# MYBOARD_04-Other_Function.net
KiCad netlist of a schematic drawn in Altium Designer
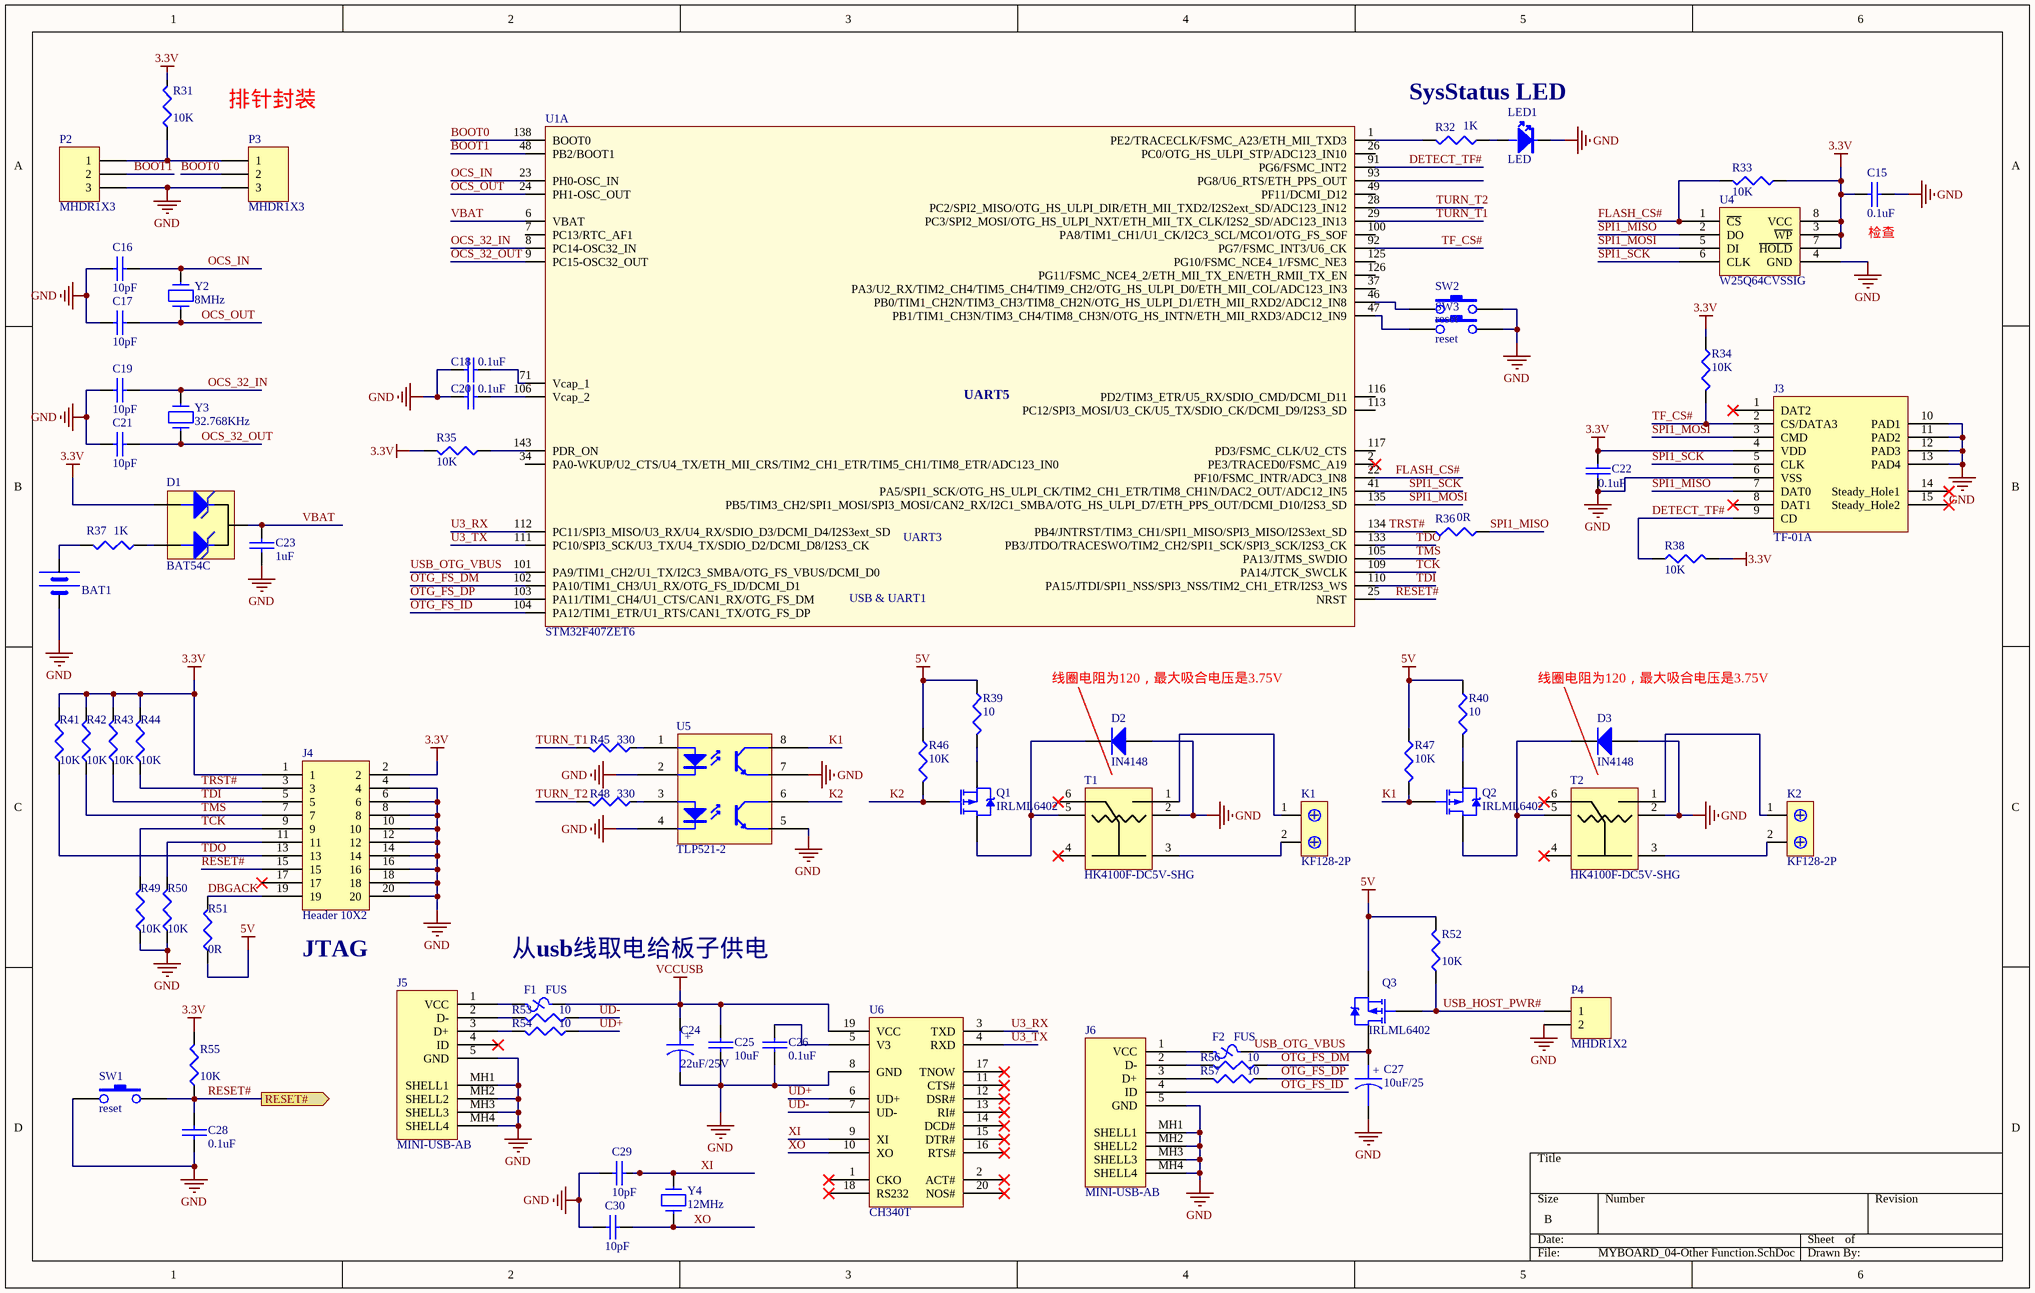
[diagram p0: MYBOARD_04-Other Function.SchDoc]

(export (version "E")
  (design (tool "Eeschema 10.0.6"))
  (components
    (comp (ref "BAT1") (value "BATT") (footprint "BC501SM") (libsource (lib "ortho fixture") (part "BAT")))
    (comp (ref "C15")
      (value "0.1uF")
      (footprint "C0603_DWS")
      (description "Capacitor")
      (libsource (lib "ortho fixture") (part "CAP"))
    )
    (comp (ref "C16")
      (value "10pF")
      (footprint "C0603_DWS")
      (description "Capacitor")
      (libsource (lib "ortho fixture") (part "CAP"))
    )
    (comp (ref "C17")
      (value "10pF")
      (footprint "C0603_DWS")
      (description "Capacitor")
      (libsource (lib "ortho fixture") (part "CAP"))
    )
    (comp (ref "C18")
      (value "0.1uF")
      (footprint "C0603_DWS")
      (description "Capacitor")
      (libsource (lib "ortho fixture") (part "CAP"))
    )
    (comp (ref "C19")
      (value "10pF")
      (footprint "C0603_DWS")
      (description "Capacitor")
      (libsource (lib "ortho fixture") (part "CAP"))
    )
    (comp (ref "C20")
      (value "0.1uF")
      (footprint "C0603_DWS")
      (description "Capacitor")
      (libsource (lib "ortho fixture") (part "CAP"))
    )
    (comp (ref "C21")
      (value "10pF")
      (footprint "C0603_DWS")
      (description "Capacitor")
      (libsource (lib "ortho fixture") (part "CAP"))
    )
    (comp (ref "C22")
      (value "0.1uF")
      (footprint "C0603_DWS")
      (description "Capacitor")
      (libsource (lib "ortho fixture") (part "CAP"))
    )
    (comp (ref "C23")
      (value "1uF")
      (footprint "C0603_DWS")
      (description "Capacitor")
      (libsource (lib "ortho fixture") (part "CAP"))
    )
    (comp (ref "C24")
      (value "22uF/25V")
      (footprint "CAPAE7053X56M")
      (description "Capacitor")
      (libsource (lib "ortho fixture") (part "CAPACITOR POL"))
    )
    (comp (ref "C25")
      (value "10uF")
      (footprint "C0603_DWS")
      (description "Capacitor")
      (libsource (lib "ortho fixture") (part "CAP"))
    )
    (comp (ref "C26")
      (value "0.1uF")
      (footprint "C0603_DWS")
      (description "Capacitor")
      (libsource (lib "ortho fixture") (part "CAP"))
    )
    (comp (ref "C27")
      (value "10uF/25")
      (footprint "CAPAE7053X56M")
      (description "Aluminum Electrolytic Capacitor SMD  Footprint:SizeCode_C")
      (fields
        (field (name "MANUFACTURER") "Panasonic")
        (field (name "MANUFACTURER PART NUMBER") "EEE1EA100SR")
      )
      (libsource (lib "ortho fixture") (part "EEE1EA100SR"))
    )
    (comp (ref "C28")
      (value "0.1uF")
      (footprint "C0603_DWS")
      (description "Capacitor")
      (libsource (lib "ortho fixture") (part "CAP"))
    )
    (comp (ref "C29")
      (value "10pF")
      (footprint "C0603_DWS")
      (description "Capacitor")
      (libsource (lib "ortho fixture") (part "CAP"))
    )
    (comp (ref "C30")
      (value "10pF")
      (footprint "C0603_DWS")
      (description "Capacitor")
      (libsource (lib "ortho fixture") (part "CAP"))
    )
    (comp (ref "D1")
      (value "BAT54C")
      (footprint "BAT54C")
      (description "Diode")
      (libsource (lib "ortho fixture") (part "BAT54C"))
    )
    (comp (ref "D2")
      (value "IN4148")
      (footprint "1N4148WS")
      (description "High Conductance Fast Diode")
      (fields (field (name "PUBLISHER") "Altium Limited"))
      (libsource (lib "ortho fixture") (part "Diode 1N914"))
    )
    (comp (ref "D3")
      (value "IN4148")
      (footprint "1N4148WS")
      (description "High Conductance Fast Diode")
      (fields (field (name "PUBLISHER") "Altium Limited"))
      (libsource (lib "ortho fixture") (part "Diode 1N914"))
    )
    (comp (ref "F1") (value "FUS") (footprint "1206") (libsource (lib "ortho fixture") (part "FUS")))
    (comp (ref "F2") (value "FUS") (footprint "1206") (libsource (lib "ortho fixture") (part "FUS")))
    (comp (ref "J3")
      (value "TF-01A")
      (footprint "TF-01A")
      (description "TF card socket,9pin,minisd socket,mirco sd socket,")
      (libsource (lib "ortho fixture") (part "TF-01A"))
    )
    (comp (ref "J4")
      (value "Header 10X2")
      (footprint "HDR2X10H")
      (description "Header, 10-Pin, Dual row")
      (libsource (lib "ortho fixture") (part "Header 10X2"))
    )
    (comp (ref "J5")
      (value "MINI-USB-AB")
      (footprint "MINI-B")
      (description "MINI USB AB 5pin SMT")
      (libsource (lib "ortho fixture") (part "MINI-USB-AB"))
    )
    (comp (ref "J6")
      (value "MINI-USB-AB")
      (footprint "MINI-B")
      (description "MINI USB AB 5pin SMT")
      (libsource (lib "ortho fixture") (part "MINI-USB-AB"))
    )
    (comp (ref "K1")
      (value "KF128-2P")
      (footprint "KF128-2P")
      (description "pitch 5mm,blue, 2 pin,length 10mm")
      (libsource (lib "ortho fixture") (part "KF128-2P"))
    )
    (comp (ref "K2")
      (value "KF128-2P")
      (footprint "KF128-2P")
      (description "pitch 5mm,blue, 2 pin,length 10mm")
      (libsource (lib "ortho fixture") (part "KF128-2P"))
    )
    (comp (ref "LED1") (value "LED") (footprint "LED-0603") (libsource (lib "ortho fixture") (part "LED")))
    (comp (ref "P2")
      (value "MHDR1X3")
      (footprint "HN1X3")
      (description "Header, 3-Pin")
      (fields (field (name "PUBLISHER") "Altium Limited"))
      (libsource (lib "") (part "MHDR1X3_1"))
    )
    (comp (ref "P3")
      (value "MHDR1X3")
      (footprint "HN1X3")
      (description "Header, 3-Pin")
      (fields (field (name "PUBLISHER") "Altium Limited"))
      (libsource (lib "Miscellaneous Connectors") (part "MHDR1X3"))
    )
    (comp (ref "P4")
      (value "MHDR1X2")
      (footprint "JP1")
      (description "Header, 2-Pin")
      (fields (field (name "PUBLISHER") "Altium Limited"))
      (libsource (lib "Miscellaneous Connectors") (part "MHDR1X2"))
    )
    (comp (ref "Q1")
      (value "IRLML6402")
      (footprint "SOTFL95P264X112-3N")
      (description "HEXFET Power MOSFET")
      (fields (field (name "PUBLISHER") "Altium Limited"))
      (libsource (lib "IR Discrete MOSFET - Power") (part "IRLML6401"))
    )
    (comp (ref "Q2")
      (value "IRLML6402")
      (footprint "SOTFL95P264X112-3N")
      (description "HEXFET Power MOSFET")
      (fields (field (name "PUBLISHER") "Altium Limited"))
      (libsource (lib "IR Discrete MOSFET - Power") (part "IRLML6401"))
    )
    (comp (ref "Q3")
      (value "IRLML6402")
      (footprint "SOTFL95P264X112-3N")
      (description "HEXFET Power MOSFET")
      (fields (field (name "PUBLISHER") "Altium Limited"))
      (libsource (lib "IR Discrete MOSFET - Power") (part "IRLML6401"))
    )
    (comp (ref "R31")
      (value "10K")
      (footprint "R0603_5MIL_DWS")
      (description "Resistor")
      (fields (field (name "Comment") "Res3") (field (name "PUBLISHER") "Altium Limited"))
      (libsource (lib "Miscellaneous Devices") (part "Res3"))
    )
    (comp (ref "R32")
      (value "1K")
      (footprint "R0603_5MIL_DWS")
      (description "Resistor")
      (fields (field (name "Comment") "Res3") (field (name "PUBLISHER") "Altium Limited"))
      (libsource (lib "Miscellaneous Devices") (part "Res3"))
    )
    (comp (ref "R33")
      (value "10K")
      (footprint "R0603_5MIL_DWS")
      (description "Resistor")
      (fields (field (name "Comment") "Res3") (field (name "PUBLISHER") "Altium Limited"))
      (libsource (lib "Miscellaneous Devices") (part "Res3"))
    )
    (comp (ref "R34")
      (value "10K")
      (footprint "R0603_5MIL_DWS")
      (description "Resistor")
      (fields (field (name "Comment") "Res3") (field (name "PUBLISHER") "Altium Limited"))
      (libsource (lib "Miscellaneous Devices") (part "Res3"))
    )
    (comp (ref "R35")
      (value "10K")
      (footprint "R0603_5MIL_DWS")
      (description "Resistor")
      (fields (field (name "Comment") "Res3") (field (name "PUBLISHER") "Altium Limited"))
      (libsource (lib "Miscellaneous Devices") (part "Res3"))
    )
    (comp (ref "R36")
      (value "0R")
      (footprint "R0603_5MIL_DWS")
      (description "Resistor")
      (fields (field (name "Comment") "Res3") (field (name "PUBLISHER") "Altium Limited"))
      (libsource (lib "Miscellaneous Devices") (part "Res3"))
    )
    (comp (ref "R37")
      (value "1K")
      (footprint "R0603_5MIL_DWS")
      (description "Resistor")
      (fields (field (name "Comment") "Res3") (field (name "PUBLISHER") "Altium Limited"))
      (libsource (lib "Miscellaneous Devices") (part "Res3"))
    )
    (comp (ref "R38")
      (value "10K")
      (footprint "R0603_5MIL_DWS")
      (description "Resistor")
      (fields (field (name "Comment") "Res3") (field (name "PUBLISHER") "Altium Limited"))
      (libsource (lib "Miscellaneous Devices") (part "Res3"))
    )
    (comp (ref "R39")
      (value "10")
      (footprint "R0603_5MIL_DWS")
      (description "Resistor")
      (fields (field (name "Comment") "Res3") (field (name "PUBLISHER") "Altium Limited"))
      (libsource (lib "Miscellaneous Devices") (part "Res3"))
    )
    (comp (ref "R40")
      (value "10")
      (footprint "R0603_5MIL_DWS")
      (description "Resistor")
      (fields (field (name "Comment") "Res3") (field (name "PUBLISHER") "Altium Limited"))
      (libsource (lib "Miscellaneous Devices") (part "Res3"))
    )
    (comp (ref "R41")
      (value "10K")
      (footprint "R0603_5MIL_DWS")
      (description "Resistor")
      (fields (field (name "Comment") "Res3") (field (name "PUBLISHER") "Altium Limited"))
      (libsource (lib "Miscellaneous Devices") (part "Res3"))
    )
    (comp (ref "R42")
      (value "10K")
      (footprint "R0603_5MIL_DWS")
      (description "Resistor")
      (fields (field (name "Comment") "Res3") (field (name "PUBLISHER") "Altium Limited"))
      (libsource (lib "Miscellaneous Devices") (part "Res3"))
    )
    (comp (ref "R43")
      (value "10K")
      (footprint "R0603_5MIL_DWS")
      (description "Resistor")
      (fields (field (name "Comment") "Res3") (field (name "PUBLISHER") "Altium Limited"))
      (libsource (lib "Miscellaneous Devices") (part "Res3"))
    )
    (comp (ref "R44")
      (value "10K")
      (footprint "R0603_5MIL_DWS")
      (description "Resistor")
      (fields (field (name "Comment") "Res3") (field (name "PUBLISHER") "Altium Limited"))
      (libsource (lib "Miscellaneous Devices") (part "Res3"))
    )
    (comp (ref "R45")
      (value "330")
      (footprint "R0603_5MIL_DWS")
      (description "Resistor")
      (fields (field (name "Comment") "Res3") (field (name "PUBLISHER") "Altium Limited"))
      (libsource (lib "Miscellaneous Devices") (part "Res3"))
    )
    (comp (ref "R46")
      (value "10K")
      (footprint "R0603_5MIL_DWS")
      (description "Resistor")
      (fields (field (name "Comment") "Res3") (field (name "PUBLISHER") "Altium Limited"))
      (libsource (lib "Miscellaneous Devices") (part "Res3"))
    )
    (comp (ref "R47")
      (value "10K")
      (footprint "R0603_5MIL_DWS")
      (description "Resistor")
      (fields (field (name "Comment") "Res3") (field (name "PUBLISHER") "Altium Limited"))
      (libsource (lib "Miscellaneous Devices") (part "Res3"))
    )
    (comp (ref "R48")
      (value "330")
      (footprint "R0603_5MIL_DWS")
      (description "Resistor")
      (fields (field (name "Comment") "Res3") (field (name "PUBLISHER") "Altium Limited"))
      (libsource (lib "Miscellaneous Devices") (part "Res3"))
    )
    (comp (ref "R49")
      (value "10K")
      (footprint "R0603_5MIL_DWS")
      (description "Resistor")
      (fields (field (name "Comment") "Res3") (field (name "PUBLISHER") "Altium Limited"))
      (libsource (lib "Miscellaneous Devices") (part "Res3"))
    )
    (comp (ref "R50")
      (value "10K")
      (footprint "R0603_5MIL_DWS")
      (description "Resistor")
      (fields (field (name "Comment") "Res3") (field (name "PUBLISHER") "Altium Limited"))
      (libsource (lib "Miscellaneous Devices") (part "Res3"))
    )
    (comp (ref "R51")
      (value "0R")
      (footprint "R0603_5MIL_DWS")
      (description "Resistor")
      (fields (field (name "Comment") "Res3") (field (name "PUBLISHER") "Altium Limited"))
      (libsource (lib "Miscellaneous Devices") (part "Res3"))
    )
    (comp (ref "R52")
      (value "10K")
      (footprint "R0603_5MIL_DWS")
      (description "Resistor")
      (fields (field (name "Comment") "Res3") (field (name "PUBLISHER") "Altium Limited"))
      (libsource (lib "Miscellaneous Devices") (part "Res3"))
    )
    (comp (ref "R53")
      (value "10")
      (footprint "R0603_5MIL_DWS")
      (description "Resistor")
      (fields (field (name "Comment") "Res3") (field (name "PUBLISHER") "Altium Limited"))
      (libsource (lib "Miscellaneous Devices") (part "Res3"))
    )
    (comp (ref "R54")
      (value "10")
      (footprint "R0603_5MIL_DWS")
      (description "Resistor")
      (fields (field (name "Comment") "Res3") (field (name "PUBLISHER") "Altium Limited"))
      (libsource (lib "Miscellaneous Devices") (part "Res3"))
    )
    (comp (ref "R55")
      (value "10K")
      (footprint "R0603_5MIL_DWS")
      (description "Resistor")
      (fields (field (name "Comment") "Res3") (field (name "PUBLISHER") "Altium Limited"))
      (libsource (lib "Miscellaneous Devices") (part "Res3"))
    )
    (comp (ref "R56")
      (value "10")
      (footprint "R0603_5MIL_DWS")
      (description "Resistor")
      (fields (field (name "Comment") "Res3") (field (name "PUBLISHER") "Altium Limited"))
      (libsource (lib "Miscellaneous Devices") (part "Res3"))
    )
    (comp (ref "R57")
      (value "10")
      (footprint "R0603_5MIL_DWS")
      (description "Resistor")
      (fields (field (name "Comment") "Res3") (field (name "PUBLISHER") "Altium Limited"))
      (libsource (lib "Miscellaneous Devices") (part "Res3"))
    )
    (comp (ref "SW1")
      (value "reset")
      (footprint "SW-TAKT_6X3.5_SMD")
      (description "贴片按键")
      (libsource (lib "ortho fixture") (part "SW-PB"))
    )
    (comp (ref "SW2")
      (value "reset")
      (footprint "SW-TAKT_6X3.5_SMD")
      (description "贴片按键")
      (libsource (lib "ortho fixture") (part "SW-PB"))
    )
    (comp (ref "SW3")
      (value "reset")
      (footprint "SW-TAKT_6X3.5_SMD")
      (description "贴片按键")
      (libsource (lib "ortho fixture") (part "SW-PB"))
    )
    (comp (ref "T1")
      (value "HK4100F-DC5V-SHG")
      (footprint "HK4100F")
      (libsource (lib "ortho fixture") (part "HK4100F"))
    )
    (comp (ref "T2")
      (value "HK4100F-DC5V-SHG")
      (footprint "HK4100F")
      (libsource (lib "ortho fixture") (part "HK4100F"))
    )
    (comp (ref "U1")
      (value "STM32F407ZET6")
      (footprint "LQFP144")
      (libsource (lib "ortho fixture") (part "STM32F407ZET6"))
    )
    (comp (ref "U4")
      (value "W25Q64CVSSIG")
      (footprint "SOIC-8")
      (description "64M Bits,SOIC-8,FLASH")
      (libsource (lib "ortho fixture") (part "W25Q64CVSSIG"))
    )
    (comp (ref "U5")
      (value "TLP521-2")
      (footprint "DIP-8")
      (libsource (lib "ortho fixture") (part "TLP521-2"))
    )
    (comp (ref "U6") (value "CH340T") (footprint "SSOP-20") (libsource (lib "ortho fixture") (part "CH340T")))
    (comp (ref "Y2")
      (value "8MHz")
      (footprint "CRYSTAL22.1184_3*5 - duplicate")
      (description "无源晶振")
      (libsource (lib "ortho fixture") (part "CRYSTAL"))
    )
    (comp (ref "Y3")
      (value "32.768KHz")
      (footprint "CRYSTAL22.1184_3*5 - duplicate")
      (description "无源晶振")
      (libsource (lib "ortho fixture") (part "CRYSTAL"))
    )
    (comp (ref "Y4")
      (value "12MHz")
      (footprint "HC49/SMD2_THIN")
      (description "无源晶振")
      (libsource (lib "ortho fixture") (part "CRYSTAL"))
    )
  )
  (nets
    (net (code "1") (name "/BOOT0") (class "Default")
      (node (ref "P3") (pin "2") (pinfunction "2_2") (pintype "passive"))
      (node (ref "U1") (pin "138") (pinfunction "BOOT0_138") (pintype "passive"))
    )
    (net (code "2") (name "/BOOT1") (class "Default")
      (node (ref "P2") (pin "2") (pinfunction "2_2") (pintype "passive"))
      (node (ref "U1") (pin "48") (pinfunction "PB2/BOOT1_48") (pintype "passive"))
    )
    (net (code "3") (name "/DBGACK") (class "Default")
      (node (ref "J4") (pin "19") (pinfunction "19_19") (pintype "passive"))
      (node (ref "R51") (pin "2") (pinfunction "2_2") (pintype "passive"))
    )
    (net (code "4") (name "/DETECT_TF#") (class "Default")
      (node (ref "J3") (pin "9") (pinfunction "CD_9") (pintype "power_in"))
      (node (ref "R38") (pin "1") (pinfunction "1_1") (pintype "passive"))
      (node (ref "U1") (pin "91") (pinfunction "PG6/FSMC_INT2_91") (pintype "passive"))
    )
    (net (code "5") (name "/FLASH_CS#") (class "Default")
      (node (ref "R33") (pin "2") (pinfunction "2_2") (pintype "passive"))
      (node (ref "U1") (pin "22") (pinfunction "PF10/FSMC_INTR/ADC3_IN8_22") (pintype "passive"))
      (node (ref "U4") (pin "1") (pinfunction "~{CS}_1") (pintype "power_in"))
    )
    (net (code "6") (name "/K1") (class "Default")
      (node (ref "Q2") (pin "1") (pinfunction "G_1") (pintype "passive"))
      (node (ref "R47") (pin "2") (pinfunction "2_2") (pintype "passive"))
      (node (ref "U5") (pin "8") (pinfunction "C_8") (pintype "passive"))
    )
    (net (code "7") (name "/K2") (class "Default")
      (node (ref "Q1") (pin "1") (pinfunction "G_1") (pintype "passive"))
      (node (ref "R46") (pin "2") (pinfunction "2_2") (pintype "passive"))
      (node (ref "U5") (pin "6") (pinfunction "C_6") (pintype "passive"))
    )
    (net (code "8") (name "/OCS_32_IN") (class "Default")
      (node (ref "C19") (pin "2") (pinfunction "2_2") (pintype "passive"))
      (node (ref "U1") (pin "8") (pinfunction "PC14-OSC32_IN_8") (pintype "passive"))
      (node (ref "Y3") (pin "2") (pinfunction "2_2") (pintype "passive"))
    )
    (net (code "9") (name "/OCS_32_OUT") (class "Default")
      (node (ref "C21") (pin "2") (pinfunction "2_2") (pintype "passive"))
      (node (ref "U1") (pin "9") (pinfunction "PC15-OSC32_OUT_9") (pintype "passive"))
      (node (ref "Y3") (pin "1") (pinfunction "1_1") (pintype "passive"))
    )
    (net (code "10") (name "/OCS_IN") (class "Default")
      (node (ref "C16") (pin "2") (pinfunction "2_2") (pintype "passive"))
      (node (ref "U1") (pin "23") (pinfunction "PH0-OSC_IN_23") (pintype "passive"))
      (node (ref "Y2") (pin "2") (pinfunction "2_2") (pintype "passive"))
    )
    (net (code "11") (name "/OCS_OUT") (class "Default")
      (node (ref "C17") (pin "2") (pinfunction "2_2") (pintype "passive"))
      (node (ref "U1") (pin "24") (pinfunction "PH1-OSC_OUT_24") (pintype "passive"))
      (node (ref "Y2") (pin "1") (pinfunction "1_1") (pintype "passive"))
    )
    (net (code "12") (name "/OTG_FS_DM") (class "Default")
      (node (ref "R56") (pin "1") (pinfunction "1_1") (pintype "passive"))
      (node (ref "U1") (pin "102") (pinfunction "PA10/TIM1_CH3/U1_RX/OTG_FS_ID/DCMI_D1_102") (pintype "passive"))
    )
    (net (code "13") (name "/OTG_FS_DP") (class "Default")
      (node (ref "R57") (pin "1") (pinfunction "1_1") (pintype "passive"))
      (node (ref "U1") (pin "103") (pinfunction "PA11/TIM1_CH4/U1_CTS/CAN1_RX/OTG_FS_DM_103") (pintype "passive"))
    )
    (net (code "14") (name "/OTG_FS_ID") (class "Default")
      (node (ref "J6") (pin "4") (pinfunction "ID_4") (pintype "passive"))
      (node (ref "U1") (pin "104") (pinfunction "PA12/TIM1_ETR/U1_RTS/CAN1_TX/OTG_FS_DP_104") (pintype "passive"))
    )
    (net (code "15") (name "/RESET#") (class "Default")
      (node (ref "C28") (pin "1") (pinfunction "1_1") (pintype "passive"))
      (node (ref "J4") (pin "15") (pinfunction "15_15") (pintype "passive"))
      (node (ref "R55") (pin "1") (pinfunction "1_1") (pintype "passive"))
      (node (ref "SW1") (pin "P$2") (pinfunction "2_P$2") (pintype "passive"))
      (node (ref "U1") (pin "25") (pinfunction "NRST_25") (pintype "passive"))
    )
    (net (code "16") (name "/SPI1_MISO") (class "Default")
      (node (ref "J3") (pin "7") (pinfunction "DAT0_7") (pintype "power_in"))
      (node (ref "R36") (pin "1") (pinfunction "1_1") (pintype "passive"))
      (node (ref "U4") (pin "2") (pinfunction "DO_2") (pintype "power_in"))
    )
    (net (code "17") (name "/SPI1_MOSI") (class "Default")
      (node (ref "J3") (pin "3") (pinfunction "CMD_3") (pintype "power_in"))
      (node (ref "U1") (pin "135") (pinfunction "PB5/TIM3_CH2/SPI1_MOSI/SPI3_MOSI/CAN2_RX/I2C1_SMBA/OTG_HS_ULPI_D7/ETH_PPS_OUT/DCMI_D10/I2S3_SD_135") (pintype "passive"))
      (node (ref "U4") (pin "5") (pinfunction "DI_5") (pintype "power_in"))
    )
    (net (code "18") (name "/SPI1_SCK") (class "Default")
      (node (ref "J3") (pin "5") (pinfunction "CLK_5") (pintype "power_in"))
      (node (ref "U1") (pin "41") (pinfunction "PA5/SPI1_SCK/OTG_HS_ULPI_CK/TIM2_CH1_ETR/TIM8_CH1N/DAC2_OUT/ADC12_IN5_41") (pintype "passive"))
      (node (ref "U4") (pin "6") (pinfunction "CLK_6") (pintype "power_in"))
    )
    (net (code "19") (name "/TCK") (class "Default")
      (node (ref "J4") (pin "9") (pinfunction "9_9") (pintype "passive"))
      (node (ref "R49") (pin "2") (pinfunction "2_2") (pintype "passive"))
      (node (ref "U1") (pin "109") (pinfunction "PA14/JTCK_SWCLK_109") (pintype "passive"))
    )
    (net (code "20") (name "/TDI") (class "Default")
      (node (ref "J4") (pin "5") (pinfunction "5_5") (pintype "passive"))
      (node (ref "R43") (pin "1") (pinfunction "1_1") (pintype "passive"))
      (node (ref "U1") (pin "110") (pinfunction "PA15/JTDI/SPI1_NSS/SPI3_NSS/TIM2_CH1_ETR/I2S3_WS_110") (pintype "passive"))
    )
    (net (code "21") (name "/TDO") (class "Default")
      (node (ref "J4") (pin "13") (pinfunction "13_13") (pintype "passive"))
      (node (ref "R41") (pin "1") (pinfunction "1_1") (pintype "passive"))
      (node (ref "U1") (pin "133") (pinfunction "PB3/JTDO/TRACESWO/TIM2_CH2/SPI1_SCK/SPI3_SCK/I2S3_CK_133") (pintype "passive"))
    )
    (net (code "22") (name "/TF_CS#") (class "Default")
      (node (ref "J3") (pin "2") (pinfunction "CS/DATA3_2") (pintype "power_in"))
      (node (ref "R34") (pin "2") (pinfunction "2_2") (pintype "passive"))
      (node (ref "U1") (pin "92") (pinfunction "PG7/FSMC_INT3/U6_CK_92") (pintype "passive"))
    )
    (net (code "23") (name "/TMS") (class "Default")
      (node (ref "J4") (pin "7") (pinfunction "7_7") (pintype "passive"))
      (node (ref "R42") (pin "1") (pinfunction "1_1") (pintype "passive"))
      (node (ref "U1") (pin "105") (pinfunction "PA13/JTMS_SWDIO_105") (pintype "passive"))
    )
    (net (code "24") (name "/TRST#") (class "Default")
      (node (ref "J4") (pin "3") (pinfunction "3_3") (pintype "passive"))
      (node (ref "R36") (pin "2") (pinfunction "2_2") (pintype "passive"))
      (node (ref "R44") (pin "1") (pinfunction "1_1") (pintype "passive"))
      (node (ref "U1") (pin "134") (pinfunction "PB4/JNTRST/TIM3_CH1/SPI1_MISO/SPI3_MISO/I2S3ext_SD_134") (pintype "passive"))
    )
    (net (code "25") (name "/TURN_T1") (class "Default")
      (node (ref "R45") (pin "2") (pinfunction "2_2") (pintype "passive"))
      (node (ref "U1") (pin "29") (pinfunction "PC3/SPI2_MOSI/OTG_HS_ULPI_NXT/ETH_MII_TX_CLK/I2S2_SD/ADC123_IN13_29") (pintype "passive"))
    )
    (net (code "26") (name "/TURN_T2") (class "Default")
      (node (ref "R48") (pin "2") (pinfunction "2_2") (pintype "passive"))
      (node (ref "U1") (pin "28") (pinfunction "PC2/SPI2_MISO/OTG_HS_ULPI_DIR/ETH_MII_TXD2/I2S2ext_SD/ADC123_IN12_28") (pintype "passive"))
    )
    (net (code "27") (name "/U3_RX") (class "Default")
      (node (ref "U1") (pin "112") (pinfunction "PC11/SPI3_MISO/U3_RX/U4_RX/SDIO_D3/DCMI_D4/I2S3ext_SD_112") (pintype "passive"))
      (node (ref "U6") (pin "3") (pinfunction "TXD_3") (pintype "passive"))
    )
    (net (code "28") (name "/U3_TX") (class "Default")
      (node (ref "U1") (pin "111") (pinfunction "PC10/SPI3_SCK/U3_TX/U4_TX/SDIO_D2/DCMI_D8/I2S3_CK_111") (pintype "passive"))
      (node (ref "U6") (pin "4") (pinfunction "RXD_4") (pintype "passive"))
    )
    (net (code "29") (name "/UD+") (class "Default")
      (node (ref "R54") (pin "1") (pinfunction "1_1") (pintype "passive"))
      (node (ref "U6") (pin "6") (pinfunction "UD+_6") (pintype "passive"))
    )
    (net (code "30") (name "/UD-") (class "Default")
      (node (ref "R53") (pin "1") (pinfunction "1_1") (pintype "passive"))
      (node (ref "U6") (pin "7") (pinfunction "UD-_7") (pintype "passive"))
    )
    (net (code "31") (name "/USB_HOST_PWR#") (class "Default")
      (node (ref "P4") (pin "1") (pinfunction "1_1") (pintype "passive"))
      (node (ref "Q3") (pin "1") (pinfunction "G_1") (pintype "passive"))
      (node (ref "R52") (pin "1") (pinfunction "1_1") (pintype "passive"))
    )
    (net (code "32") (name "/USB_OTG_VBUS") (class "Default")
      (node (ref "C27") (pin "1") (pinfunction "1_1") (pintype "passive"))
      (node (ref "F2") (pin "2") (pinfunction "2_2") (pintype "passive"))
      (node (ref "Q3") (pin "3") (pinfunction "D_3") (pintype "passive"))
      (node (ref "U1") (pin "101") (pinfunction "PA9/TIM1_CH2/U1_TX/I2C3_SMBA/OTG_FS_VBUS/DCMI_D0_101") (pintype "passive"))
    )
    (net (code "33") (name "/VBAT") (class "Default")
      (node (ref "C23") (pin "1") (pinfunction "1_1") (pintype "passive"))
      (node (ref "D1") (pin "3") (pinfunction "3_3") (pintype "passive"))
      (node (ref "U1") (pin "6") (pinfunction "VBAT_6") (pintype "passive"))
    )
    (net (code "34") (name "/XI") (class "Default")
      (node (ref "C29") (pin "2") (pinfunction "2_2") (pintype "passive"))
      (node (ref "U6") (pin "9") (pinfunction "XI_9") (pintype "passive"))
      (node (ref "Y4") (pin "2") (pinfunction "2_2") (pintype "passive"))
    )
    (net (code "35") (name "/XO") (class "Default")
      (node (ref "C30") (pin "2") (pinfunction "2_2") (pintype "passive"))
      (node (ref "U6") (pin "10") (pinfunction "XO_10") (pintype "passive"))
      (node (ref "Y4") (pin "1") (pinfunction "1_1") (pintype "passive"))
    )
    (net (code "36") (name "3.3V") (class "Default")
      (node (ref "C15") (pin "1") (pinfunction "1_1") (pintype "passive"))
      (node (ref "C22") (pin "2") (pinfunction "2_2") (pintype "passive"))
      (node (ref "D1") (pin "1") (pinfunction "1_1") (pintype "passive"))
      (node (ref "J3") (pin "4") (pinfunction "VDD_4") (pintype "power_in"))
      (node (ref "J4") (pin "1") (pinfunction "1_1") (pintype "passive"))
      (node (ref "J4") (pin "2") (pinfunction "2_2") (pintype "passive"))
      (node (ref "R31") (pin "2") (pinfunction "2_2") (pintype "passive"))
      (node (ref "R33") (pin "1") (pinfunction "1_1") (pintype "passive"))
      (node (ref "R34") (pin "1") (pinfunction "1_1") (pintype "passive"))
      (node (ref "R35") (pin "2") (pinfunction "2_2") (pintype "passive"))
      (node (ref "R38") (pin "2") (pinfunction "2_2") (pintype "passive"))
      (node (ref "R41") (pin "2") (pinfunction "2_2") (pintype "passive"))
      (node (ref "R42") (pin "2") (pinfunction "2_2") (pintype "passive"))
      (node (ref "R43") (pin "2") (pinfunction "2_2") (pintype "passive"))
      (node (ref "R44") (pin "2") (pinfunction "2_2") (pintype "passive"))
      (node (ref "R55") (pin "2") (pinfunction "2_2") (pintype "passive"))
      (node (ref "U4") (pin "3") (pinfunction "~{WP}_3") (pintype "power_in"))
      (node (ref "U4") (pin "7") (pinfunction "~{HOLD}_7") (pintype "power_in"))
      (node (ref "U4") (pin "8") (pinfunction "VCC_8") (pintype "power_in"))
    )
    (net (code "37") (name "5V") (class "Default")
      (node (ref "Q3") (pin "2") (pinfunction "S_2") (pintype "passive"))
      (node (ref "R39") (pin "1") (pinfunction "1_1") (pintype "passive"))
      (node (ref "R40") (pin "1") (pinfunction "1_1") (pintype "passive"))
      (node (ref "R46") (pin "1") (pinfunction "1_1") (pintype "passive"))
      (node (ref "R47") (pin "1") (pinfunction "1_1") (pintype "passive"))
      (node (ref "R51") (pin "1") (pinfunction "1_1") (pintype "passive"))
      (node (ref "R52") (pin "2") (pinfunction "2_2") (pintype "passive"))
    )
    (net (code "38") (name "GND") (class "Default")
      (node (ref "BAT1") (pin "2") (pinfunction "GND_2") (pintype "passive"))
      (node (ref "C15") (pin "2") (pinfunction "2_2") (pintype "passive"))
      (node (ref "C16") (pin "1") (pinfunction "1_1") (pintype "passive"))
      (node (ref "C17") (pin "1") (pinfunction "1_1") (pintype "passive"))
      (node (ref "C18") (pin "1") (pinfunction "1_1") (pintype "passive"))
      (node (ref "C19") (pin "1") (pinfunction "1_1") (pintype "passive"))
      (node (ref "C20") (pin "1") (pinfunction "1_1") (pintype "passive"))
      (node (ref "C21") (pin "1") (pinfunction "1_1") (pintype "passive"))
      (node (ref "C22") (pin "1") (pinfunction "1_1") (pintype "passive"))
      (node (ref "C23") (pin "2") (pinfunction "2_2") (pintype "passive"))
      (node (ref "C24") (pin "2") (pinfunction "2_2") (pintype "passive"))
      (node (ref "C25") (pin "2") (pinfunction "2_2") (pintype "passive"))
      (node (ref "C26") (pin "2") (pinfunction "2_2") (pintype "passive"))
      (node (ref "C27") (pin "2") (pinfunction "2_2") (pintype "passive"))
      (node (ref "C28") (pin "2") (pinfunction "2_2") (pintype "passive"))
      (node (ref "C29") (pin "1") (pinfunction "1_1") (pintype "passive"))
      (node (ref "C30") (pin "1") (pinfunction "1_1") (pintype "passive"))
      (node (ref "D2") (pin "2") (pinfunction "A_2") (pintype "passive"))
      (node (ref "D3") (pin "2") (pinfunction "A_2") (pintype "passive"))
      (node (ref "J3") (pin "10") (pinfunction "PAD1_10") (pintype "power_in"))
      (node (ref "J3") (pin "11") (pinfunction "PAD2_11") (pintype "power_in"))
      (node (ref "J3") (pin "12") (pinfunction "PAD3_12") (pintype "power_in"))
      (node (ref "J3") (pin "13") (pinfunction "PAD4_13") (pintype "power_in"))
      (node (ref "J3") (pin "6") (pinfunction "VSS_6") (pintype "power_in"))
      (node (ref "J4") (pin "10") (pinfunction "10_10") (pintype "passive"))
      (node (ref "J4") (pin "12") (pinfunction "12_12") (pintype "passive"))
      (node (ref "J4") (pin "14") (pinfunction "14_14") (pintype "passive"))
      (node (ref "J4") (pin "16") (pinfunction "16_16") (pintype "passive"))
      (node (ref "J4") (pin "18") (pinfunction "18_18") (pintype "passive"))
      (node (ref "J4") (pin "20") (pinfunction "20_20") (pintype "passive"))
      (node (ref "J4") (pin "4") (pinfunction "4_4") (pintype "passive"))
      (node (ref "J4") (pin "6") (pinfunction "6_6") (pintype "passive"))
      (node (ref "J4") (pin "8") (pinfunction "8_8") (pintype "passive"))
      (node (ref "J5") (pin "5") (pinfunction "GND_5") (pintype "passive"))
      (node (ref "J5") (pin "MH1") (pinfunction "SHELL1_MH1") (pintype "power_in"))
      (node (ref "J5") (pin "MH2") (pinfunction "SHELL2_MH2") (pintype "power_in"))
      (node (ref "J5") (pin "MH3") (pinfunction "SHELL3_MH3") (pintype "power_in"))
      (node (ref "J5") (pin "MH4") (pinfunction "SHELL4_MH4") (pintype "power_in"))
      (node (ref "J6") (pin "5") (pinfunction "GND_5") (pintype "passive"))
      (node (ref "J6") (pin "MH1") (pinfunction "SHELL1_MH1") (pintype "power_in"))
      (node (ref "J6") (pin "MH2") (pinfunction "SHELL2_MH2") (pintype "power_in"))
      (node (ref "J6") (pin "MH3") (pinfunction "SHELL3_MH3") (pintype "power_in"))
      (node (ref "J6") (pin "MH4") (pinfunction "SHELL4_MH4") (pintype "power_in"))
      (node (ref "LED1") (pin "C") (pinfunction "C_C") (pintype "passive"))
      (node (ref "P2") (pin "3") (pinfunction "3_3") (pintype "passive"))
      (node (ref "P3") (pin "3") (pinfunction "3_3") (pintype "passive"))
      (node (ref "P4") (pin "2") (pinfunction "2_2") (pintype "passive"))
      (node (ref "R49") (pin "1") (pinfunction "1_1") (pintype "passive"))
      (node (ref "R50") (pin "1") (pinfunction "1_1") (pintype "passive"))
      (node (ref "SW1") (pin "P$1") (pinfunction "1_P$1") (pintype "passive"))
      (node (ref "SW2") (pin "P$2") (pinfunction "2_P$2") (pintype "passive"))
      (node (ref "SW3") (pin "P$2") (pinfunction "2_P$2") (pintype "passive"))
      (node (ref "T1") (pin "2") (pinfunction "COIL1_2") (pintype "passive"))
      (node (ref "T2") (pin "2") (pinfunction "COIL1_2") (pintype "passive"))
      (node (ref "U4") (pin "4") (pinfunction "GND_4") (pintype "power_in"))
      (node (ref "U5") (pin "2") (pinfunction "K_2") (pintype "passive"))
      (node (ref "U5") (pin "4") (pinfunction "K_4") (pintype "passive"))
      (node (ref "U5") (pin "5") (pinfunction "E_5") (pintype "passive"))
      (node (ref "U5") (pin "7") (pinfunction "E_7") (pintype "passive"))
      (node (ref "U6") (pin "8") (pinfunction "GND_8") (pintype "passive"))
    )
    (net (code "39") (name "Net-(BAT1-VCC)") (class "Default")
      (node (ref "BAT1") (pin "1") (pinfunction "VCC_1") (pintype "passive"))
      (node (ref "R37") (pin "2") (pinfunction "2_2") (pintype "passive"))
    )
    (net (code "40") (name "Net-(D1-Pad2)") (class "Default")
      (node (ref "D1") (pin "2") (pinfunction "2_2") (pintype "passive"))
      (node (ref "R37") (pin "1") (pinfunction "1_1") (pintype "passive"))
    )
    (net (code "41") (name "Net-(D2-K)") (class "Default")
      (node (ref "D2") (pin "1") (pinfunction "K_1") (pintype "passive"))
      (node (ref "Q1") (pin "3") (pinfunction "D_3") (pintype "passive"))
      (node (ref "T1") (pin "5") (pinfunction "COIL2_5") (pintype "passive"))
    )
    (net (code "42") (name "Net-(D3-K)") (class "Default")
      (node (ref "D3") (pin "1") (pinfunction "K_1") (pintype "passive"))
      (node (ref "Q2") (pin "3") (pinfunction "D_3") (pintype "passive"))
      (node (ref "T2") (pin "5") (pinfunction "COIL2_5") (pintype "passive"))
    )
    (net (code "43") (name "Net-(J4-Pad11)") (class "Default")
      (node (ref "J4") (pin "11") (pinfunction "11_11") (pintype "passive"))
      (node (ref "R50") (pin "2") (pinfunction "2_2") (pintype "passive"))
    )
    (net (code "44") (name "Net-(J5-D+)") (class "Default")
      (node (ref "J5") (pin "3") (pinfunction "D+_3") (pintype "passive"))
      (node (ref "R54") (pin "2") (pinfunction "2_2") (pintype "passive"))
    )
    (net (code "45") (name "Net-(J5-D-)") (class "Default")
      (node (ref "J5") (pin "2") (pinfunction "D-_2") (pintype "passive"))
      (node (ref "R53") (pin "2") (pinfunction "2_2") (pintype "passive"))
    )
    (net (code "46") (name "Net-(J5-VCC)") (class "Default")
      (node (ref "F1") (pin "1") (pinfunction "1_1") (pintype "passive"))
      (node (ref "J5") (pin "1") (pinfunction "VCC_1") (pintype "passive"))
    )
    (net (code "47") (name "Net-(J6-D+)") (class "Default")
      (node (ref "J6") (pin "3") (pinfunction "D+_3") (pintype "passive"))
      (node (ref "R57") (pin "2") (pinfunction "2_2") (pintype "passive"))
    )
    (net (code "48") (name "Net-(J6-D-)") (class "Default")
      (node (ref "J6") (pin "2") (pinfunction "D-_2") (pintype "passive"))
      (node (ref "R56") (pin "2") (pinfunction "2_2") (pintype "passive"))
    )
    (net (code "49") (name "Net-(J6-VCC)") (class "Default")
      (node (ref "F2") (pin "1") (pinfunction "1_1") (pintype "passive"))
      (node (ref "J6") (pin "1") (pinfunction "VCC_1") (pintype "passive"))
    )
    (net (code "50") (name "Net-(K1-Pad2)") (class "Default")
      (node (ref "K1") (pin "2") (pinfunction "2_2") (pintype "passive"))
      (node (ref "T1") (pin "3") (pinfunction "COM_3") (pintype "passive"))
    )
    (net (code "51") (name "Net-(K2-Pad2)") (class "Default")
      (node (ref "K2") (pin "2") (pinfunction "2_2") (pintype "passive"))
      (node (ref "T2") (pin "3") (pinfunction "COM_3") (pintype "passive"))
    )
    (net (code "52") (name "Net-(LED1-1)") (class "Default")
      (node (ref "LED1") (pin "A") (pinfunction "1_A") (pintype "passive"))
      (node (ref "R32") (pin "1") (pinfunction "1_1") (pintype "passive"))
    )
    (net (code "53") (name "Net-(P2-Pad1)") (class "Default")
      (node (ref "P2") (pin "1") (pinfunction "1_1") (pintype "passive"))
      (node (ref "P3") (pin "1") (pinfunction "1_1") (pintype "passive"))
      (node (ref "R31") (pin "1") (pinfunction "1_1") (pintype "passive"))
    )
    (net (code "54") (name "Net-(Q1-S)") (class "Default")
      (node (ref "Q1") (pin "2") (pinfunction "S_2") (pintype "passive"))
      (node (ref "R39") (pin "2") (pinfunction "2_2") (pintype "passive"))
    )
    (net (code "55") (name "Net-(Q2-S)") (class "Default")
      (node (ref "Q2") (pin "2") (pinfunction "S_2") (pintype "passive"))
      (node (ref "R40") (pin "2") (pinfunction "2_2") (pintype "passive"))
    )
    (net (code "56") (name "Net-(R45-Pad1)") (class "Default")
      (node (ref "R45") (pin "1") (pinfunction "1_1") (pintype "passive"))
      (node (ref "U5") (pin "1") (pinfunction "A_1") (pintype "passive"))
    )
    (net (code "57") (name "Net-(R48-Pad1)") (class "Default")
      (node (ref "R48") (pin "1") (pinfunction "1_1") (pintype "passive"))
      (node (ref "U5") (pin "3") (pinfunction "A_3") (pintype "passive"))
    )
    (net (code "58") (name "Net-(SW2-1)") (class "Default")
      (node (ref "SW2") (pin "P$1") (pinfunction "1_P$1") (pintype "passive"))
      (node (ref "U1") (pin "46") (pinfunction "PB0/TIM1_CH2N/TIM3_CH3/TIM8_CH2N/OTG_HS_ULPI_D1/ETH_MII_RXD2/ADC12_IN8_46") (pintype "passive"))
    )
    (net (code "59") (name "Net-(SW3-1)") (class "Default")
      (node (ref "SW3") (pin "P$1") (pinfunction "1_P$1") (pintype "passive"))
      (node (ref "U1") (pin "47") (pinfunction "PB1/TIM1_CH3N/TIM3_CH4/TIM8_CH3N/OTG_HS_INTN/ETH_MII_RXD3/ADC12_IN9_47") (pintype "passive"))
    )
    (net (code "60") (name "Net-(T1-NO)") (class "Default")
      (node (ref "K1") (pin "1") (pinfunction "1_1") (pintype "passive"))
      (node (ref "T1") (pin "1") (pinfunction "NO_1") (pintype "passive"))
    )
    (net (code "61") (name "Net-(T2-NO)") (class "Default")
      (node (ref "K2") (pin "1") (pinfunction "1_1") (pintype "passive"))
      (node (ref "T2") (pin "1") (pinfunction "NO_1") (pintype "passive"))
    )
    (net (code "62") (name "Net-(U1A-PDR_ON)") (class "Default")
      (node (ref "R35") (pin "1") (pinfunction "1_1") (pintype "passive"))
      (node (ref "U1") (pin "143") (pinfunction "PDR_ON_143") (pintype "passive"))
    )
    (net (code "63") (name "Net-(U1A-PE2{slash}TRACECLK{slash}FSMC_A23{slash}ETH_MII_TXD3)") (class "Default")
      (node (ref "R32") (pin "2") (pinfunction "2_2") (pintype "passive"))
      (node (ref "U1") (pin "1") (pinfunction "PE2/TRACECLK/FSMC_A23/ETH_MII_TXD3_1") (pintype "passive"))
    )
    (net (code "64") (name "Net-(U1A-Vcap_1)") (class "Default")
      (node (ref "C18") (pin "2") (pinfunction "2_2") (pintype "passive"))
      (node (ref "U1") (pin "71") (pinfunction "Vcap_1_71") (pintype "passive"))
    )
    (net (code "65") (name "Net-(U1A-Vcap_2)") (class "Default")
      (node (ref "C20") (pin "2") (pinfunction "2_2") (pintype "passive"))
      (node (ref "U1") (pin "106") (pinfunction "Vcap_2_106") (pintype "passive"))
    )
    (net (code "66") (name "Net-(U6-V3)") (class "Default")
      (node (ref "C26") (pin "1") (pinfunction "1_1") (pintype "passive"))
      (node (ref "U6") (pin "5") (pinfunction "V3_5") (pintype "passive"))
    )
    (net (code "67") (name "VCCUSB") (class "Default")
      (node (ref "C24") (pin "1") (pinfunction "1_1") (pintype "passive"))
      (node (ref "C25") (pin "1") (pinfunction "1_1") (pintype "passive"))
      (node (ref "F1") (pin "2") (pinfunction "2_2") (pintype "passive"))
      (node (ref "U6") (pin "19") (pinfunction "VCC_19") (pintype "passive"))
    )
    (net (code "68") (name "unconnected-(J3-DAT1-Pad8)") (class "Default")
      (node (ref "J3") (pin "8") (pinfunction "DAT1_8") (pintype "power_in+no_connect"))
    )
    (net (code "69") (name "unconnected-(J3-DAT2-Pad1)") (class "Default")
      (node (ref "J3") (pin "1") (pinfunction "DAT2_1") (pintype "power_in+no_connect"))
    )
    (net (code "70") (name "unconnected-(J3-Steady_Hole1-Pad14)") (class "Default")
      (node (ref "J3") (pin "14") (pinfunction "Steady_Hole1_14") (pintype "power_in+no_connect"))
    )
    (net (code "71") (name "unconnected-(J3-Steady_Hole2-Pad15)") (class "Default")
      (node (ref "J3") (pin "15") (pinfunction "Steady_Hole2_15") (pintype "power_in+no_connect"))
    )
    (net (code "72") (name "unconnected-(J4-Pad17)") (class "Default")
      (node (ref "J4") (pin "17") (pinfunction "17_17") (pintype "passive+no_connect"))
    )
    (net (code "73") (name "unconnected-(J5-ID-Pad4)") (class "Default")
      (node (ref "J5") (pin "4") (pinfunction "ID_4") (pintype "passive+no_connect"))
    )
    (net (code "74") (name "unconnected-(T1-COM-Pad4)") (class "Default")
      (node (ref "T1") (pin "4") (pinfunction "COM_4") (pintype "passive+no_connect"))
    )
    (net (code "75") (name "unconnected-(T1-NC-Pad6)") (class "Default")
      (node (ref "T1") (pin "6") (pinfunction "NC_6") (pintype "passive+no_connect"))
    )
    (net (code "76") (name "unconnected-(T2-COM-Pad4)") (class "Default")
      (node (ref "T2") (pin "4") (pinfunction "COM_4") (pintype "passive+no_connect"))
    )
    (net (code "77") (name "unconnected-(T2-NC-Pad6)") (class "Default")
      (node (ref "T2") (pin "6") (pinfunction "NC_6") (pintype "passive+no_connect"))
    )
    (net (code "78") (name "unconnected-(U1A-PA0-WKUP{slash}U2_CTS{slash}U4_TX{slash}ETH_MII_CRS{slash}TIM2_CH1_ETR{slash}TIM5_CH1{slash}TIM8_ETR{slash}ADC123_IN0-Pad34)") (class "Default")
      (node (ref "U1") (pin "34") (pinfunction "PA0-WKUP/U2_CTS/U4_TX/ETH_MII_CRS/TIM2_CH1_ETR/TIM5_CH1/TIM8_ETR/ADC123_IN0_34") (pintype "passive"))
    )
    (net (code "79") (name "unconnected-(U1A-PA3{slash}U2_RX{slash}TIM2_CH4{slash}TIM5_CH4{slash}TIM9_CH2{slash}OTG_HS_ULPI_D0{slash}ETH_MII_COL{slash}ADC123_IN3-Pad37)") (class "Default")
      (node (ref "U1") (pin "37") (pinfunction "PA3/U2_RX/TIM2_CH4/TIM5_CH4/TIM9_CH2/OTG_HS_ULPI_D0/ETH_MII_COL/ADC123_IN3_37") (pintype "passive"))
    )
    (net (code "80") (name "unconnected-(U1A-PA8{slash}TIM1_CH1{slash}U1_CK{slash}I2C3_SCL{slash}MCO1{slash}OTG_FS_SOF-Pad100)") (class "Default")
      (node (ref "U1") (pin "100") (pinfunction "PA8/TIM1_CH1/U1_CK/I2C3_SCL/MCO1/OTG_FS_SOF_100") (pintype "passive"))
    )
    (net (code "81") (name "unconnected-(U1A-PC0{slash}OTG_HS_ULPI_STP{slash}ADC123_IN10-Pad26)") (class "Default")
      (node (ref "U1") (pin "26") (pinfunction "PC0/OTG_HS_ULPI_STP/ADC123_IN10_26") (pintype "passive"))
    )
    (net (code "82") (name "unconnected-(U1A-PC12{slash}SPI3_MOSI{slash}U3_CK{slash}U5_TX{slash}SDIO_CK{slash}DCMI_D9{slash}I2S3_SD-Pad113)") (class "Default")
      (node (ref "U1") (pin "113") (pinfunction "PC12/SPI3_MOSI/U3_CK/U5_TX/SDIO_CK/DCMI_D9/I2S3_SD_113") (pintype "passive"))
    )
    (net (code "83") (name "unconnected-(U1A-PC13{slash}RTC_AF1-Pad7)") (class "Default")
      (node (ref "U1") (pin "7") (pinfunction "PC13/RTC_AF1_7") (pintype "passive"))
    )
    (net (code "84") (name "unconnected-(U1A-PD2{slash}TIM3_ETR{slash}U5_RX{slash}SDIO_CMD{slash}DCMI_D11-Pad116)") (class "Default")
      (node (ref "U1") (pin "116") (pinfunction "PD2/TIM3_ETR/U5_RX/SDIO_CMD/DCMI_D11_116") (pintype "passive"))
    )
    (net (code "85") (name "unconnected-(U1A-PD3{slash}FSMC_CLK{slash}U2_CTS-Pad117)") (class "Default")
      (node (ref "U1") (pin "117") (pinfunction "PD3/FSMC_CLK/U2_CTS_117") (pintype "passive"))
    )
    (net (code "86") (name "unconnected-(U1A-PE3{slash}TRACED0{slash}FSMC_A19-Pad2)") (class "Default")
      (node (ref "U1") (pin "2") (pinfunction "PE3/TRACED0/FSMC_A19_2") (pintype "passive+no_connect"))
    )
    (net (code "87") (name "unconnected-(U1A-PF11{slash}DCMI_D12-Pad49)") (class "Default")
      (node (ref "U1") (pin "49") (pinfunction "PF11/DCMI_D12_49") (pintype "passive"))
    )
    (net (code "88") (name "unconnected-(U1A-PG8{slash}U6_RTS{slash}ETH_PPS_OUT-Pad93)") (class "Default")
      (node (ref "U1") (pin "93") (pinfunction "PG8/U6_RTS/ETH_PPS_OUT_93") (pintype "passive"))
    )
    (net (code "89") (name "unconnected-(U1A-PG10{slash}FSMC_NCE4_1{slash}FSMC_NE3-Pad125)") (class "Default")
      (node (ref "U1") (pin "125") (pinfunction "PG10/FSMC_NCE4_1/FSMC_NE3_125") (pintype "passive"))
    )
    (net (code "90") (name "unconnected-(U1A-PG11{slash}FSMC_NCE4_2{slash}ETH_MII_TX_EN{slash}ETH_RMII_TX_EN-Pad126)") (class "Default")
      (node (ref "U1") (pin "126") (pinfunction "PG11/FSMC_NCE4_2/ETH_MII_TX_EN/ETH_RMII_TX_EN_126") (pintype "passive"))
    )
    (net (code "91") (name "unconnected-(U6-ACT#-Pad2)") (class "Default")
      (node (ref "U6") (pin "2") (pinfunction "ACT#_2") (pintype "passive+no_connect"))
    )
    (net (code "92") (name "unconnected-(U6-CKO-Pad1)") (class "Default")
      (node (ref "U6") (pin "1") (pinfunction "CKO_1") (pintype "passive+no_connect"))
    )
    (net (code "93") (name "unconnected-(U6-CTS#-Pad11)") (class "Default")
      (node (ref "U6") (pin "11") (pinfunction "CTS#_11") (pintype "passive+no_connect"))
    )
    (net (code "94") (name "unconnected-(U6-DCD#-Pad14)") (class "Default")
      (node (ref "U6") (pin "14") (pinfunction "DCD#_14") (pintype "passive+no_connect"))
    )
    (net (code "95") (name "unconnected-(U6-DSR#-Pad12)") (class "Default")
      (node (ref "U6") (pin "12") (pinfunction "DSR#_12") (pintype "passive+no_connect"))
    )
    (net (code "96") (name "unconnected-(U6-DTR#-Pad15)") (class "Default")
      (node (ref "U6") (pin "15") (pinfunction "DTR#_15") (pintype "passive+no_connect"))
    )
    (net (code "97") (name "unconnected-(U6-NOS#-Pad20)") (class "Default")
      (node (ref "U6") (pin "20") (pinfunction "NOS#_20") (pintype "passive+no_connect"))
    )
    (net (code "98") (name "unconnected-(U6-RI#-Pad13)") (class "Default")
      (node (ref "U6") (pin "13") (pinfunction "RI#_13") (pintype "passive+no_connect"))
    )
    (net (code "99") (name "unconnected-(U6-RS232-Pad18)") (class "Default")
      (node (ref "U6") (pin "18") (pinfunction "RS232_18") (pintype "passive+no_connect"))
    )
    (net (code "100") (name "unconnected-(U6-RTS#-Pad16)") (class "Default")
      (node (ref "U6") (pin "16") (pinfunction "RTS#_16") (pintype "passive+no_connect"))
    )
    (net (code "101") (name "unconnected-(U6-TNOW-Pad17)") (class "Default")
      (node (ref "U6") (pin "17") (pinfunction "TNOW_17") (pintype "passive+no_connect"))
    )
  )
)
